# sample_holder.net
KiCad netlist of a schematic drawn in EAGLE
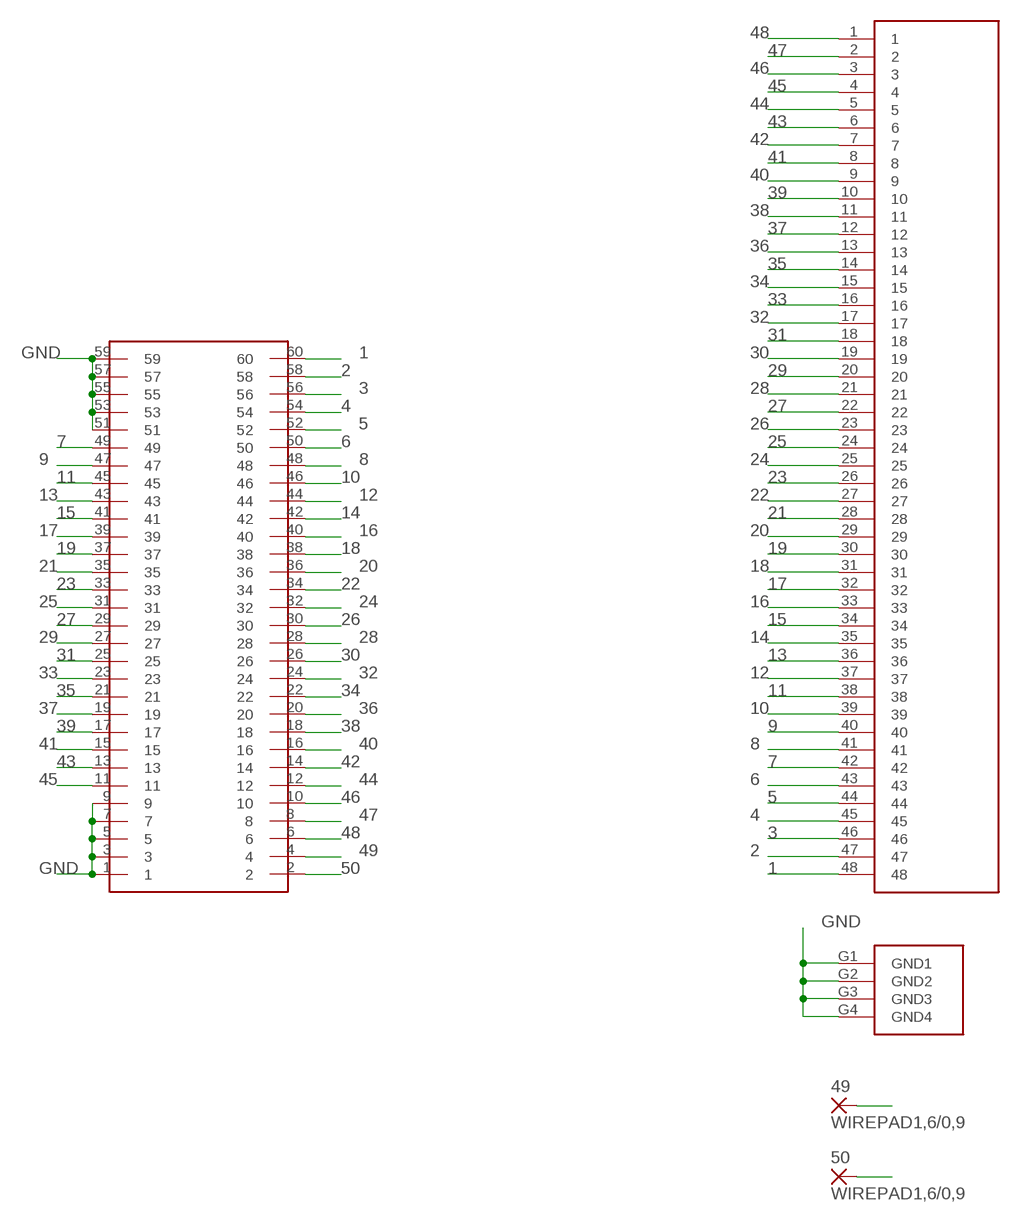
[diagram p0: schematic, sheet 1]

(export (version "E")
  (design (tool "Eeschema 10.0.6"))
  (components
    (comp (ref "49")
      (value "WIREPAD1,6/0,9")
      (footprint "eagle-import:1,6_0,9")
      (libsource (lib "eagle-import") (part "WIREPAD1,6/0,9"))
    )
    (comp (ref "50")
      (value "WIREPAD1,6/0,9")
      (footprint "eagle-import:1,6_0,9")
      (libsource (lib "eagle-import") (part "WIREPAD1,6/0,9"))
    )
    (comp (ref "U$1")
      (value "MEC5-030-CARD-ALL")
      (footprint "eagle-import:MEC-030-CARD-ALL")
      (libsource (lib "eagle-import") (part "MEC5-030-CARD-ALL"))
    )
    (comp (ref "U$2")
      (value "FOLKLAB-48PADS")
      (footprint "eagle-import:FOLKLAB-48PADS")
      (libsource (lib "eagle-import") (part "FOLKLAB-48PADS"))
    )
  )
  (nets
    (net (code "1") (name "/1") (class "Default")
      (node (ref "U$1") (pin "60") (pinfunction "60_60") (pintype "bidirectional"))
      (node (ref "U$2") (pin "48") (pinfunction "48_48") (pintype "bidirectional"))
    )
    (net (code "2") (name "/2") (class "Default")
      (node (ref "U$1") (pin "58") (pinfunction "58_58") (pintype "bidirectional"))
      (node (ref "U$2") (pin "47") (pinfunction "47_47") (pintype "bidirectional"))
    )
    (net (code "3") (name "/3") (class "Default")
      (node (ref "U$1") (pin "56") (pinfunction "56_56") (pintype "bidirectional"))
      (node (ref "U$2") (pin "46") (pinfunction "46_46") (pintype "bidirectional"))
    )
    (net (code "4") (name "/4") (class "Default")
      (node (ref "U$1") (pin "54") (pinfunction "54_54") (pintype "bidirectional"))
      (node (ref "U$2") (pin "45") (pinfunction "45_45") (pintype "bidirectional"))
    )
    (net (code "5") (name "/5") (class "Default")
      (node (ref "U$1") (pin "52") (pinfunction "52_52") (pintype "bidirectional"))
      (node (ref "U$2") (pin "44") (pinfunction "44_44") (pintype "bidirectional"))
    )
    (net (code "6") (name "/6") (class "Default")
      (node (ref "U$1") (pin "50") (pinfunction "50_50") (pintype "bidirectional"))
      (node (ref "U$2") (pin "43") (pinfunction "43_43") (pintype "bidirectional"))
    )
    (net (code "7") (name "/7") (class "Default")
      (node (ref "U$1") (pin "49") (pinfunction "49_49") (pintype "bidirectional"))
      (node (ref "U$2") (pin "42") (pinfunction "42_42") (pintype "bidirectional"))
    )
    (net (code "8") (name "/8") (class "Default")
      (node (ref "U$1") (pin "48") (pinfunction "48_48") (pintype "bidirectional"))
      (node (ref "U$2") (pin "41") (pinfunction "41_41") (pintype "bidirectional"))
    )
    (net (code "9") (name "/9") (class "Default")
      (node (ref "U$1") (pin "47") (pinfunction "47_47") (pintype "bidirectional"))
      (node (ref "U$2") (pin "40") (pinfunction "40_40") (pintype "bidirectional"))
    )
    (net (code "10") (name "/10") (class "Default")
      (node (ref "U$1") (pin "46") (pinfunction "46_46") (pintype "bidirectional"))
      (node (ref "U$2") (pin "39") (pinfunction "39_39") (pintype "bidirectional"))
    )
    (net (code "11") (name "/11") (class "Default")
      (node (ref "U$1") (pin "45") (pinfunction "45_45") (pintype "bidirectional"))
      (node (ref "U$2") (pin "38") (pinfunction "38_38") (pintype "bidirectional"))
    )
    (net (code "12") (name "/12") (class "Default")
      (node (ref "U$1") (pin "44") (pinfunction "44_44") (pintype "bidirectional"))
      (node (ref "U$2") (pin "37") (pinfunction "37_37") (pintype "bidirectional"))
    )
    (net (code "13") (name "/13") (class "Default")
      (node (ref "U$1") (pin "43") (pinfunction "43_43") (pintype "bidirectional"))
      (node (ref "U$2") (pin "36") (pinfunction "36_36") (pintype "bidirectional"))
    )
    (net (code "14") (name "/14") (class "Default")
      (node (ref "U$1") (pin "42") (pinfunction "42_42") (pintype "bidirectional"))
      (node (ref "U$2") (pin "35") (pinfunction "35_35") (pintype "bidirectional"))
    )
    (net (code "15") (name "/15") (class "Default")
      (node (ref "U$1") (pin "41") (pinfunction "41_41") (pintype "bidirectional"))
      (node (ref "U$2") (pin "34") (pinfunction "34_34") (pintype "bidirectional"))
    )
    (net (code "16") (name "/16") (class "Default")
      (node (ref "U$1") (pin "40") (pinfunction "40_40") (pintype "bidirectional"))
      (node (ref "U$2") (pin "33") (pinfunction "33_33") (pintype "bidirectional"))
    )
    (net (code "17") (name "/17") (class "Default")
      (node (ref "U$1") (pin "39") (pinfunction "39_39") (pintype "bidirectional"))
      (node (ref "U$2") (pin "32") (pinfunction "32_32") (pintype "bidirectional"))
    )
    (net (code "18") (name "/18") (class "Default")
      (node (ref "U$1") (pin "38") (pinfunction "38_38") (pintype "bidirectional"))
      (node (ref "U$2") (pin "31") (pinfunction "31_31") (pintype "bidirectional"))
    )
    (net (code "19") (name "/19") (class "Default")
      (node (ref "U$1") (pin "37") (pinfunction "37_37") (pintype "bidirectional"))
      (node (ref "U$2") (pin "30") (pinfunction "30_30") (pintype "bidirectional"))
    )
    (net (code "20") (name "/20") (class "Default")
      (node (ref "U$1") (pin "36") (pinfunction "36_36") (pintype "bidirectional"))
      (node (ref "U$2") (pin "29") (pinfunction "29_29") (pintype "bidirectional"))
    )
    (net (code "21") (name "/21") (class "Default")
      (node (ref "U$1") (pin "35") (pinfunction "35_35") (pintype "bidirectional"))
      (node (ref "U$2") (pin "28") (pinfunction "28_28") (pintype "bidirectional"))
    )
    (net (code "22") (name "/22") (class "Default")
      (node (ref "U$1") (pin "34") (pinfunction "34_34") (pintype "bidirectional"))
      (node (ref "U$2") (pin "27") (pinfunction "27_27") (pintype "bidirectional"))
    )
    (net (code "23") (name "/23") (class "Default")
      (node (ref "U$1") (pin "33") (pinfunction "33_33") (pintype "bidirectional"))
      (node (ref "U$2") (pin "26") (pinfunction "26_26") (pintype "bidirectional"))
    )
    (net (code "24") (name "/24") (class "Default")
      (node (ref "U$1") (pin "32") (pinfunction "32_32") (pintype "bidirectional"))
      (node (ref "U$2") (pin "25") (pinfunction "25_25") (pintype "bidirectional"))
    )
    (net (code "25") (name "/25") (class "Default")
      (node (ref "U$1") (pin "31") (pinfunction "31_31") (pintype "bidirectional"))
      (node (ref "U$2") (pin "24") (pinfunction "24_24") (pintype "bidirectional"))
    )
    (net (code "26") (name "/26") (class "Default")
      (node (ref "U$1") (pin "30") (pinfunction "30_30") (pintype "bidirectional"))
      (node (ref "U$2") (pin "23") (pinfunction "23_23") (pintype "bidirectional"))
    )
    (net (code "27") (name "/27") (class "Default")
      (node (ref "U$1") (pin "29") (pinfunction "29_29") (pintype "bidirectional"))
      (node (ref "U$2") (pin "22") (pinfunction "22_22") (pintype "bidirectional"))
    )
    (net (code "28") (name "/28") (class "Default")
      (node (ref "U$1") (pin "28") (pinfunction "28_28") (pintype "bidirectional"))
      (node (ref "U$2") (pin "21") (pinfunction "21_21") (pintype "bidirectional"))
    )
    (net (code "29") (name "/29") (class "Default")
      (node (ref "U$1") (pin "27") (pinfunction "27_27") (pintype "bidirectional"))
      (node (ref "U$2") (pin "20") (pinfunction "20_20") (pintype "bidirectional"))
    )
    (net (code "30") (name "/30") (class "Default")
      (node (ref "U$1") (pin "26") (pinfunction "26_26") (pintype "bidirectional"))
      (node (ref "U$2") (pin "19") (pinfunction "19_19") (pintype "bidirectional"))
    )
    (net (code "31") (name "/31") (class "Default")
      (node (ref "U$1") (pin "25") (pinfunction "25_25") (pintype "bidirectional"))
      (node (ref "U$2") (pin "18") (pinfunction "18_18") (pintype "bidirectional"))
    )
    (net (code "32") (name "/32") (class "Default")
      (node (ref "U$1") (pin "24") (pinfunction "24_24") (pintype "bidirectional"))
      (node (ref "U$2") (pin "17") (pinfunction "17_17") (pintype "bidirectional"))
    )
    (net (code "33") (name "/33") (class "Default")
      (node (ref "U$1") (pin "23") (pinfunction "23_23") (pintype "bidirectional"))
      (node (ref "U$2") (pin "16") (pinfunction "16_16") (pintype "bidirectional"))
    )
    (net (code "34") (name "/34") (class "Default")
      (node (ref "U$1") (pin "22") (pinfunction "22_22") (pintype "bidirectional"))
      (node (ref "U$2") (pin "15") (pinfunction "15_15") (pintype "bidirectional"))
    )
    (net (code "35") (name "/35") (class "Default")
      (node (ref "U$1") (pin "21") (pinfunction "21_21") (pintype "bidirectional"))
      (node (ref "U$2") (pin "14") (pinfunction "14_14") (pintype "bidirectional"))
    )
    (net (code "36") (name "/36") (class "Default")
      (node (ref "U$1") (pin "20") (pinfunction "20_20") (pintype "bidirectional"))
      (node (ref "U$2") (pin "13") (pinfunction "13_13") (pintype "bidirectional"))
    )
    (net (code "37") (name "/37") (class "Default")
      (node (ref "U$1") (pin "19") (pinfunction "19_19") (pintype "bidirectional"))
      (node (ref "U$2") (pin "12") (pinfunction "12_12") (pintype "bidirectional"))
    )
    (net (code "38") (name "/38") (class "Default")
      (node (ref "U$1") (pin "18") (pinfunction "18_18") (pintype "bidirectional"))
      (node (ref "U$2") (pin "11") (pinfunction "11_11") (pintype "bidirectional"))
    )
    (net (code "39") (name "/39") (class "Default")
      (node (ref "U$1") (pin "17") (pinfunction "17_17") (pintype "bidirectional"))
      (node (ref "U$2") (pin "10") (pinfunction "10_10") (pintype "bidirectional"))
    )
    (net (code "40") (name "/40") (class "Default")
      (node (ref "U$1") (pin "16") (pinfunction "16_16") (pintype "bidirectional"))
      (node (ref "U$2") (pin "9") (pinfunction "9_9") (pintype "bidirectional"))
    )
    (net (code "41") (name "/41") (class "Default")
      (node (ref "U$1") (pin "15") (pinfunction "15_15") (pintype "bidirectional"))
      (node (ref "U$2") (pin "8") (pinfunction "8_8") (pintype "bidirectional"))
    )
    (net (code "42") (name "/42") (class "Default")
      (node (ref "U$1") (pin "14") (pinfunction "14_14") (pintype "bidirectional"))
      (node (ref "U$2") (pin "7") (pinfunction "7_7") (pintype "bidirectional"))
    )
    (net (code "43") (name "/43") (class "Default")
      (node (ref "U$1") (pin "13") (pinfunction "13_13") (pintype "bidirectional"))
      (node (ref "U$2") (pin "6") (pinfunction "6_6") (pintype "bidirectional"))
    )
    (net (code "44") (name "/44") (class "Default")
      (node (ref "U$1") (pin "12") (pinfunction "12_12") (pintype "bidirectional"))
      (node (ref "U$2") (pin "5") (pinfunction "5_5") (pintype "bidirectional"))
    )
    (net (code "45") (name "/45") (class "Default")
      (node (ref "U$1") (pin "11") (pinfunction "11_11") (pintype "bidirectional"))
      (node (ref "U$2") (pin "4") (pinfunction "4_4") (pintype "bidirectional"))
    )
    (net (code "46") (name "/46") (class "Default")
      (node (ref "U$1") (pin "10") (pinfunction "10_10") (pintype "bidirectional"))
      (node (ref "U$2") (pin "3") (pinfunction "3_3") (pintype "bidirectional"))
    )
    (net (code "47") (name "/47") (class "Default")
      (node (ref "U$1") (pin "8") (pinfunction "8_8") (pintype "bidirectional"))
      (node (ref "U$2") (pin "2") (pinfunction "2_2") (pintype "bidirectional"))
    )
    (net (code "48") (name "/48") (class "Default")
      (node (ref "U$1") (pin "6") (pinfunction "6_6") (pintype "bidirectional"))
      (node (ref "U$2") (pin "1") (pinfunction "1_1") (pintype "bidirectional"))
    )
    (net (code "49") (name "/49") (class "Default")
      (node (ref "49") (pin "1") (pinfunction "P_1") (pintype "passive"))
      (node (ref "U$1") (pin "4") (pinfunction "4_4") (pintype "bidirectional"))
    )
    (net (code "50") (name "/50") (class "Default")
      (node (ref "50") (pin "1") (pinfunction "P_1") (pintype "passive"))
      (node (ref "U$1") (pin "2") (pinfunction "2_2") (pintype "bidirectional"))
    )
    (net (code "51") (name "/GND") (class "Default")
      (node (ref "U$1") (pin "1") (pinfunction "1_1") (pintype "bidirectional"))
      (node (ref "U$1") (pin "3") (pinfunction "3_3") (pintype "bidirectional"))
      (node (ref "U$1") (pin "5") (pinfunction "5_5") (pintype "bidirectional"))
      (node (ref "U$1") (pin "51") (pinfunction "51_51") (pintype "bidirectional"))
      (node (ref "U$1") (pin "53") (pinfunction "53_53") (pintype "bidirectional"))
      (node (ref "U$1") (pin "55") (pinfunction "55_55") (pintype "bidirectional"))
      (node (ref "U$1") (pin "57") (pinfunction "57_57") (pintype "bidirectional"))
      (node (ref "U$1") (pin "59") (pinfunction "59_59") (pintype "bidirectional"))
      (node (ref "U$1") (pin "7") (pinfunction "7_7") (pintype "bidirectional"))
      (node (ref "U$1") (pin "9") (pinfunction "9_9") (pintype "bidirectional"))
      (node (ref "U$2") (pin "G1") (pinfunction "GND1_G1") (pintype "bidirectional"))
      (node (ref "U$2") (pin "G2") (pinfunction "GND2_G2") (pintype "bidirectional"))
      (node (ref "U$2") (pin "G3") (pinfunction "GND3_G3") (pintype "bidirectional"))
      (node (ref "U$2") (pin "G4") (pinfunction "GND4_G4") (pintype "bidirectional"))
    )
  )
)
